# TLE2141-Q1.net
KiCad netlist of a schematic drawn in EAGLE
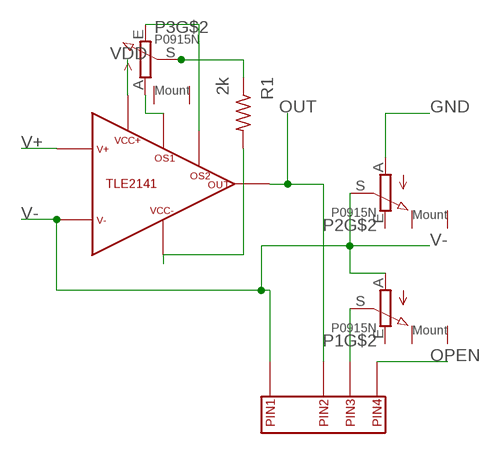
[diagram p0: schematic, sheet 1]

(export (version "E")
  (design (tool "Eeschema 10.0.6"))
  (components
    (comp (ref "P1")
      (value "P0915N")
      (footprint "eagle-import:P0915N")
      (libsource (lib "eagle-import") (part "P0915N"))
    )
    (comp (ref "P2")
      (value "P0915N")
      (footprint "eagle-import:P0915N")
      (libsource (lib "eagle-import") (part "P0915N"))
    )
    (comp (ref "P3")
      (value "P0915N")
      (footprint "eagle-import:P0915N")
      (libsource (lib "eagle-import") (part "P0915N"))
    )
    (comp (ref "R1")
      (value "2k")
      (footprint "eagle-import:0207_15")
      (libsource (lib "eagle-import") (part "R-US_0207/15"))
    )
    (comp (ref "U$1")
      (value "TLE2141-Q1")
      (footprint "eagle-import:TLE2141-Q1")
      (libsource (lib "eagle-import") (part "TLE2141-Q1"))
    )
    (comp (ref "U$2")
      (value "SP3T_SLIDE_SWITCH")
      (footprint "eagle-import:SP3T_SLIDE_SWITCH")
      (libsource (lib "eagle-import") (part "SP3T_SLIDE_SWITCH"))
    )
  )
  (nets
    (net (code "1") (name "/GND") (class "Default")
      (node (ref "P2") (pin "A") (pinfunction "A_A") (pintype "passive"))
      (node (ref "R1") (pin "2") (pinfunction "2_2") (pintype "passive"))
      (node (ref "U$1") (pin "VCC-") (pinfunction "VSS_VCC-") (pintype "bidirectional"))
    )
    (net (code "2") (name "/OPEN") (class "Default")
      (node (ref "U$2") (pin "PIN4") (pinfunction "PIN4_PIN4") (pintype "bidirectional"))
    )
    (net (code "3") (name "/OUT") (class "Default")
      (node (ref "U$1") (pin "OUT") (pinfunction "VOUT_OUT") (pintype "bidirectional"))
      (node (ref "U$2") (pin "PIN2") (pinfunction "PIN2_PIN2") (pintype "bidirectional"))
    )
    (net (code "4") (name "/V+") (class "Default")
      (node (ref "U$1") (pin "IN+") (pinfunction "V+_IN+") (pintype "bidirectional"))
    )
    (net (code "5") (name "/V-") (class "Default")
      (node (ref "P1") (pin "A") (pinfunction "A_A") (pintype "passive"))
      (node (ref "P2") (pin "S") (pinfunction "S_S") (pintype "passive"))
      (node (ref "U$1") (pin "IN-") (pinfunction "V-_IN-") (pintype "bidirectional"))
      (node (ref "U$2") (pin "PIN1") (pinfunction "PIN1_PIN1") (pintype "bidirectional"))
    )
    (net (code "6") (name "/VDD") (class "Default")
      (node (ref "U$1") (pin "VCC+") (pinfunction "VDD_VCC+") (pintype "bidirectional"))
    )
    (net (code "7") (name "Net-(P1-PadS)") (class "Default")
      (node (ref "P1") (pin "S") (pinfunction "S_S") (pintype "passive"))
      (node (ref "U$2") (pin "PIN3") (pinfunction "PIN3_PIN3") (pintype "bidirectional"))
    )
    (net (code "8") (name "Net-(P3-PadS)") (class "Default")
      (node (ref "P3") (pin "S") (pinfunction "S_S") (pintype "passive"))
      (node (ref "R1") (pin "1") (pinfunction "1_1") (pintype "passive"))
    )
    (net (code "9") (name "Net-(U$1-OS1)") (class "Default")
      (node (ref "P3") (pin "A") (pinfunction "A_A") (pintype "passive"))
      (node (ref "U$1") (pin "OFFSETN1") (pinfunction "OS1_OFFSETN1") (pintype "bidirectional"))
    )
    (net (code "10") (name "Net-(U$1-OS2)") (class "Default")
      (node (ref "P3") (pin "E") (pinfunction "E_E") (pintype "passive"))
      (node (ref "U$1") (pin "OFFSETN2") (pinfunction "OS2_OFFSETN2") (pintype "bidirectional"))
    )
    (net (code "11") (name "unconnected-(P1-PadE)") (class "Default")
      (node (ref "P1") (pin "E") (pinfunction "E_E") (pintype "passive"))
    )
    (net (code "12") (name "unconnected-(P1A-GND-PadGND@1)") (class "Default")
      (node (ref "P1") (pin "GND@1") (pinfunction "GND_GND@1") (pintype "passive"))
    )
    (net (code "13") (name "unconnected-(P1A-GND-PadGND@2)") (class "Default")
      (node (ref "P1") (pin "GND@2") (pinfunction "GND_GND@2") (pintype "passive"))
    )
    (net (code "14") (name "unconnected-(P2-PadE)") (class "Default")
      (node (ref "P2") (pin "E") (pinfunction "E_E") (pintype "passive"))
    )
    (net (code "15") (name "unconnected-(P2A-GND-PadGND@1)") (class "Default")
      (node (ref "P2") (pin "GND@1") (pinfunction "GND_GND@1") (pintype "passive"))
    )
    (net (code "16") (name "unconnected-(P2A-GND-PadGND@2)") (class "Default")
      (node (ref "P2") (pin "GND@2") (pinfunction "GND_GND@2") (pintype "passive"))
    )
    (net (code "17") (name "unconnected-(P3A-GND-PadGND@1)") (class "Default")
      (node (ref "P3") (pin "GND@1") (pinfunction "GND_GND@1") (pintype "passive"))
    )
    (net (code "18") (name "unconnected-(P3A-GND-PadGND@2)") (class "Default")
      (node (ref "P3") (pin "GND@2") (pinfunction "GND_GND@2") (pintype "passive"))
    )
  )
)
